# Proiect_TSC.net
KiCad netlist of a schematic drawn in EAGLE
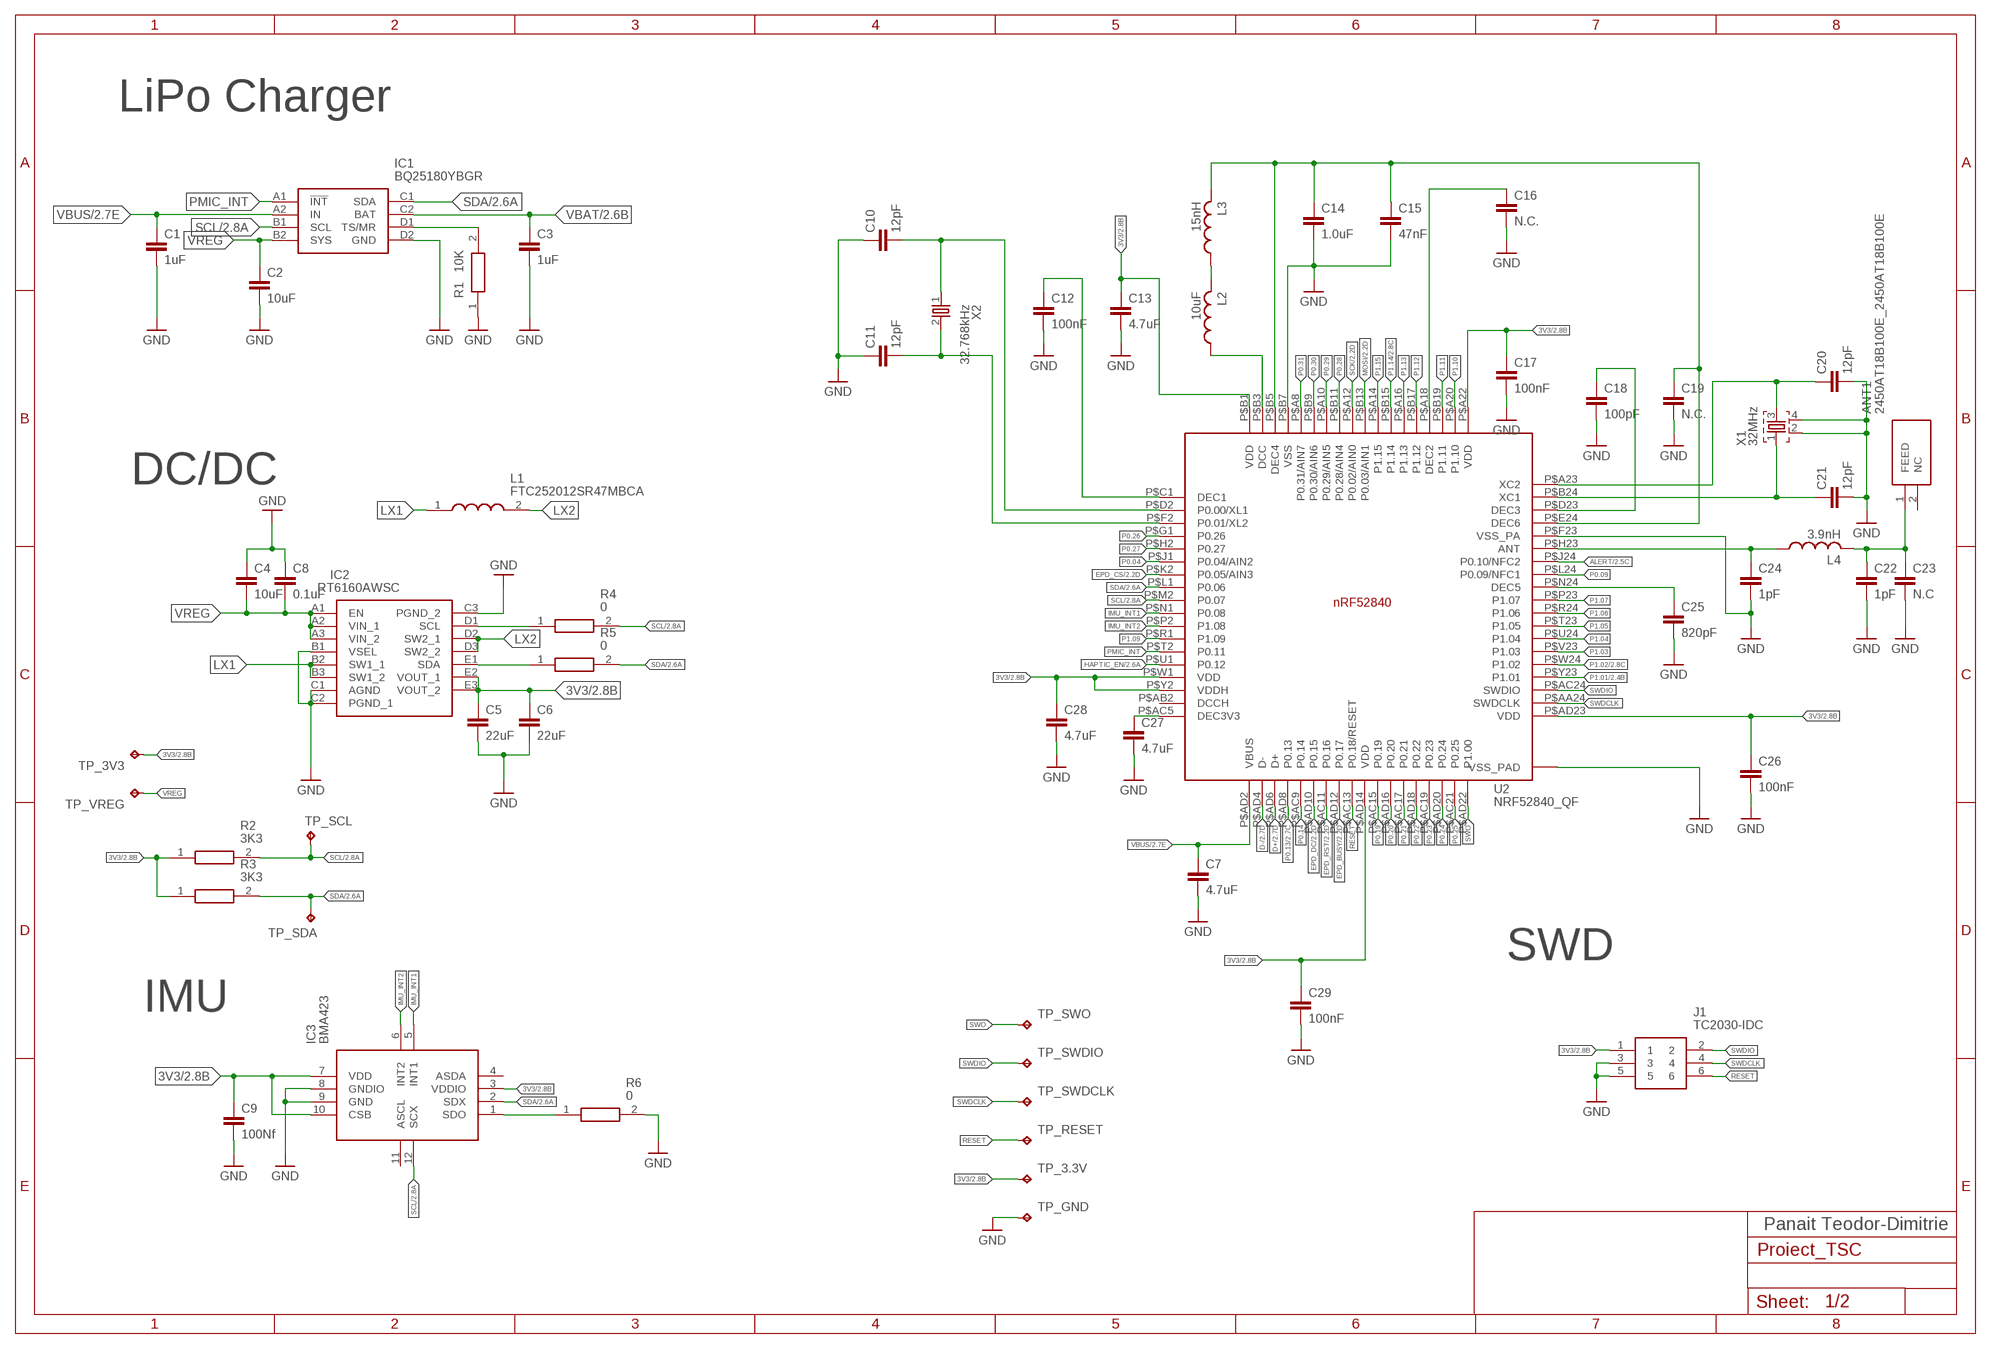
[diagram p0: schematic, sheet 1]
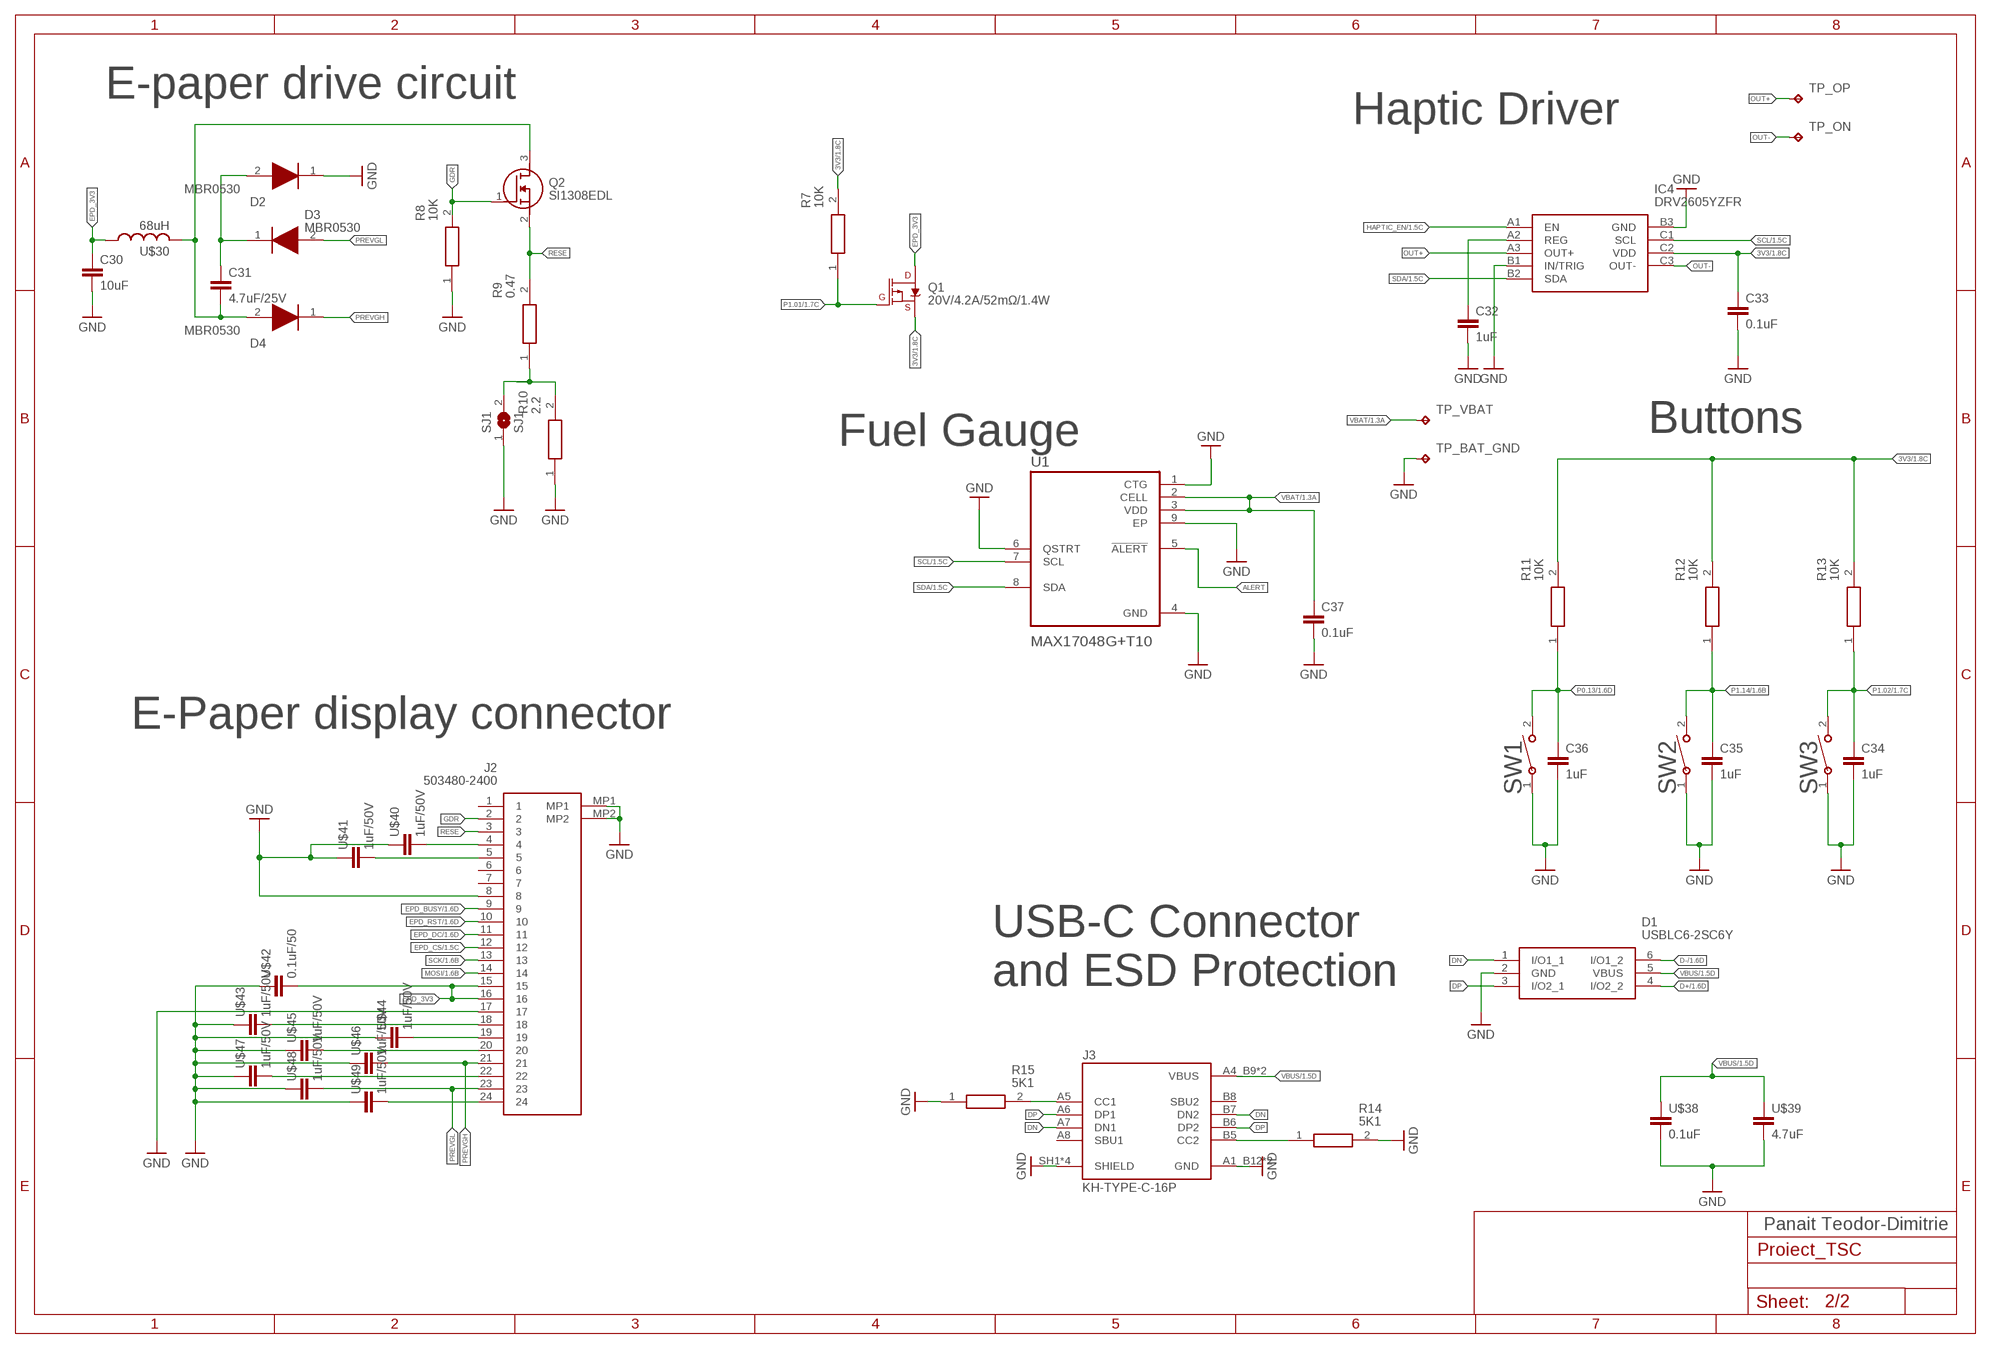
[diagram p1: schematic, sheet 2]

(export (version "E")
  (design (tool "Eeschema 10.0.6"))
  (components
    (comp (ref "C30")
      (value "10uF")
      (footprint "eagle-import:NORDIC_NRF_3_RESC0402_L")
      (libsource (lib "eagle-import") (part "NORDIC_NRF_3_CAPACITOR_0402_L"))
    )
    (comp (ref "C31")
      (value "4.7uF/25V")
      (footprint "eagle-import:NORDIC_NRF_3_RESC0402_L")
      (libsource (lib "eagle-import") (part "NORDIC_NRF_3_CAPACITOR_0402_L"))
    )
    (comp (ref "C32")
      (value "1uF")
      (footprint "eagle-import:NORDIC_NRF_3_RESC0402_L")
      (libsource (lib "eagle-import") (part "NORDIC_NRF_3_CAPACITOR_0402_L"))
    )
    (comp (ref "C33")
      (value "0.1uF")
      (footprint "eagle-import:NORDIC_NRF_3_RESC0201_L")
      (libsource (lib "eagle-import") (part "NORDIC_NRF_3_CAPACITOR_0201_L"))
    )
    (comp (ref "C34")
      (value "1uF")
      (footprint "eagle-import:NORDIC_NRF_3_RESC0402_L")
      (libsource (lib "eagle-import") (part "NORDIC_NRF_3_CAPACITOR_0402_L"))
    )
    (comp (ref "C35")
      (value "1uF")
      (footprint "eagle-import:NORDIC_NRF_3_RESC0402_L")
      (libsource (lib "eagle-import") (part "NORDIC_NRF_3_CAPACITOR_0402_L"))
    )
    (comp (ref "C36")
      (value "1uF")
      (footprint "eagle-import:NORDIC_NRF_3_RESC0402_L")
      (libsource (lib "eagle-import") (part "NORDIC_NRF_3_CAPACITOR_0402_L"))
    )
    (comp (ref "C37")
      (value "0.1uF")
      (footprint "eagle-import:NORDIC_NRF_3_RESC0201_L")
      (libsource (lib "eagle-import") (part "NORDIC_NRF_3_CAPACITOR_0201_L"))
    )
    (comp (ref "D1")
      (value "USBLC6-2SC6Y")
      (footprint "eagle-import:ESP32_C6_LIBRARY_3_SOT95P280X145-6N")
      (fields (field (name "MF") "STMicroelectronics"))
      (libsource (lib "eagle-import") (part "ESP32_C6_LIBRARY_3_USBLC6-2SC6Y"))
    )
    (comp (ref "D2")
      (value "MBR0530")
      (footprint "eagle-import:ESP32_C6_LIBRARY_5_SOD3716X135N")
      (fields (field (name "MF") "ON Semiconductor"))
      (libsource (lib "eagle-import") (part "ESP32_C6_LIBRARY_5_MBR0530"))
    )
    (comp (ref "D3")
      (value "MBR0530")
      (footprint "eagle-import:ESP32_C6_LIBRARY_5_SOD3716X135N")
      (fields (field (name "MF") "ON Semiconductor"))
      (libsource (lib "eagle-import") (part "ESP32_C6_LIBRARY_5_MBR0530"))
    )
    (comp (ref "D4")
      (value "MBR0530")
      (footprint "eagle-import:ESP32_C6_LIBRARY_5_SOD3716X135N")
      (fields (field (name "MF") "ON Semiconductor"))
      (libsource (lib "eagle-import") (part "ESP32_C6_LIBRARY_5_MBR0530"))
    )
    (comp (ref "IC4")
      (value "DRV2605YZFR")
      (footprint "eagle-import:DRV2605YZFR_BGA9C50P3X3_144X144X62")
      (libsource (lib "eagle-import") (part "DRV2605YZFR_DRV2605YZFR"))
    )
    (comp (ref "J2")
      (value "503480-2400")
      (footprint "eagle-import:503480-2400_5034802400")
      (fields (field (name "MOUSER_PART_NUMBER") "538-503480-2400"))
      (libsource (lib "eagle-import") (part "503480-2400_503480-2400"))
    )
    (comp (ref "J3")
      (value "KH-TYPE-C-16P")
      (footprint "eagle-import:KH-TYPE-C-16P_KINGHELM_KH-TYPE-C-16P")
      (fields (field (name "MF") "kinghelm"))
      (libsource (lib "eagle-import") (part "KH-TYPE-C-16P_KH-TYPE-C-16P"))
    )
    (comp (ref "Q1")
      (value "20V/4.2A/52mΩ/1.4W")
      (footprint "eagle-import:ESP32_C6_LIBRARY_4_ESP32_C6_LIBRARY_4_ESP32_C6_LIBRARY_4_ESP32_C6_LIBRARY_4_ESP32_WROVER_SPARKFUN-DISCRETESEMI_SOT23-3")
      (libsource (lib "eagle-import") (part "ESP32_C6_LIBRARY_4_ESP32_WROVER_SPARKFUN-DISCRETESEMI_MOSFET_PCH-DMG2305UX-7"))
    )
    (comp (ref "Q2")
      (value "SI1308EDL")
      (footprint "eagle-import:ESP32_C6_LIBRARY_6_SOT65P210X110-3N")
      (fields (field (name "MF") "Vishay Siliconix") (field (name "MP") "SI1308EDL-T1-GE3"))
      (libsource (lib "eagle-import") (part "ESP32_C6_LIBRARY_6_SI1308EDL-T1-GE3"))
    )
    (comp (ref "R7")
      (value "10K")
      (footprint "eagle-import:CPF0201D7K68C1_0201")
      (libsource (lib "eagle-import") (part "CPF0201D7K68C1_CPF0201D7K68C1"))
    )
    (comp (ref "R8")
      (value "10K")
      (footprint "eagle-import:CPF0201D7K68C1_0201")
      (libsource (lib "eagle-import") (part "CPF0201D7K68C1_CPF0201D7K68C1"))
    )
    (comp (ref "R9")
      (value "0.47")
      (footprint "eagle-import:CPF0201D7K68C1_0201")
      (libsource (lib "eagle-import") (part "CPF0201D7K68C1_CPF0201D7K68C1"))
    )
    (comp (ref "R10")
      (value "2.2")
      (footprint "eagle-import:CPF0201D7K68C1_0201")
      (libsource (lib "eagle-import") (part "CPF0201D7K68C1_CPF0201D7K68C1"))
    )
    (comp (ref "R11")
      (value "10K")
      (footprint "eagle-import:CPF0201D7K68C1_0201")
      (libsource (lib "eagle-import") (part "CPF0201D7K68C1_CPF0201D7K68C1"))
    )
    (comp (ref "R12")
      (value "10K")
      (footprint "eagle-import:CPF0201D7K68C1_0201")
      (libsource (lib "eagle-import") (part "CPF0201D7K68C1_CPF0201D7K68C1"))
    )
    (comp (ref "R13")
      (value "10K")
      (footprint "eagle-import:CPF0201D7K68C1_0201")
      (libsource (lib "eagle-import") (part "CPF0201D7K68C1_CPF0201D7K68C1"))
    )
    (comp (ref "R14")
      (value "5K1")
      (footprint "eagle-import:CPF0201D7K68C1_0201")
      (libsource (lib "eagle-import") (part "CPF0201D7K68C1_CPF0201D7K68C1"))
    )
    (comp (ref "R15")
      (value "5K1")
      (footprint "eagle-import:CPF0201D7K68C1_0201")
      (libsource (lib "eagle-import") (part "CPF0201D7K68C1_CPF0201D7K68C1"))
    )
    (comp (ref "SJ1")
      (value "SJ1")
      (footprint "eagle-import:ESP32_C6_LIBRARY_7_JUMPER_SJ")
      (libsource (lib "eagle-import") (part "ESP32_C6_LIBRARY_7_JUMPER_SJ"))
    )
    (comp (ref "SW1")
      (value "SW1")
      (footprint "eagle-import:2025-10-22_07-23-44_LIBRARY_SW_EVP-AKE31A_PAN")
      (fields
        (field (name "MANUFACTURER_PART_NUMBER") "EVP-AKE31A")
        (field (name "COPYRIGHT") "Copyright (C) 2025 Ultra Librarian. All rights reserved.")
      )
      (libsource (lib "eagle-import") (part "2025-10-22_07-23-44_LIBRARY_EVP-AKE31ASW_EVP-AKE31A_PAN"))
    )
    (comp (ref "SW2")
      (value "2025-10-22_07-23-44_LIBRARY_EVP-AKE31ASW_EVP-AKE31A_PAN")
      (footprint "eagle-import:2025-10-22_07-23-44_LIBRARY_SW_EVP-AKE31A_PAN")
      (fields
        (field (name "MANUFACTURER_PART_NUMBER") "EVP-AKE31A")
        (field (name "COPYRIGHT") "Copyright (C) 2025 Ultra Librarian. All rights reserved.")
      )
      (libsource (lib "eagle-import") (part "2025-10-22_07-23-44_LIBRARY_EVP-AKE31ASW_EVP-AKE31A_PAN"))
    )
    (comp (ref "SW3")
      (value "2025-10-22_07-23-44_LIBRARY_EVP-AKE31ASW_EVP-AKE31A_PAN")
      (footprint "eagle-import:2025-10-22_07-23-44_LIBRARY_SW_EVP-AKE31A_PAN")
      (fields
        (field (name "MANUFACTURER_PART_NUMBER") "EVP-AKE31A")
        (field (name "COPYRIGHT") "Copyright (C) 2025 Ultra Librarian. All rights reserved.")
      )
      (libsource (lib "eagle-import") (part "2025-10-22_07-23-44_LIBRARY_EVP-AKE31ASW_EVP-AKE31A_PAN"))
    )
    (comp (ref "TP_BAT_GND")
      (value "HECTOR_WATCH_1_TPTP20R")
      (footprint "eagle-import:HECTOR_WATCH_1_TP20R")
      (libsource (lib "eagle-import") (part "HECTOR_WATCH_1_TPTP20R"))
    )
    (comp (ref "TP_ON")
      (value "HECTOR_WATCH_1_TPTP20R")
      (footprint "eagle-import:HECTOR_WATCH_1_TP20R")
      (libsource (lib "eagle-import") (part "HECTOR_WATCH_1_TPTP20R"))
    )
    (comp (ref "TP_OP")
      (value "HECTOR_WATCH_1_TPTP20R")
      (footprint "eagle-import:HECTOR_WATCH_1_TP20R")
      (libsource (lib "eagle-import") (part "HECTOR_WATCH_1_TPTP20R"))
    )
    (comp (ref "TP_VBAT")
      (value "HECTOR_WATCH_1_TPTP20R")
      (footprint "eagle-import:HECTOR_WATCH_1_TP20R")
      (libsource (lib "eagle-import") (part "HECTOR_WATCH_1_TPTP20R"))
    )
    (comp (ref "U$30")
      (value "68uH")
      (footprint "eagle-import:NORDIC_NRF_2_RESC0201_L")
      (libsource (lib "eagle-import") (part "NORDIC_NRF_2_INDUCTOR_0201_L"))
    )
    (comp (ref "U$38")
      (value "0.1uF")
      (footprint "eagle-import:NORDIC_NRF_3_RESC0201_L")
      (libsource (lib "eagle-import") (part "NORDIC_NRF_3_CAPACITOR_0201_L"))
    )
    (comp (ref "U$39")
      (value "4.7uF")
      (footprint "eagle-import:NORDIC_NRF_3_RESC0402_L")
      (libsource (lib "eagle-import") (part "NORDIC_NRF_3_CAPACITOR_0402_L"))
    )
    (comp (ref "U$40")
      (value "1uF/50V")
      (footprint "eagle-import:NORDIC_NRF_3_RESC0402_L")
      (libsource (lib "eagle-import") (part "NORDIC_NRF_3_CAPACITOR_0402_L"))
    )
    (comp (ref "U$41")
      (value "1uF/50V")
      (footprint "eagle-import:NORDIC_NRF_3_RESC0402_L")
      (libsource (lib "eagle-import") (part "NORDIC_NRF_3_CAPACITOR_0402_L"))
    )
    (comp (ref "U$42")
      (value "0.1uF/50")
      (footprint "eagle-import:NORDIC_NRF_3_RESC0201_L")
      (libsource (lib "eagle-import") (part "NORDIC_NRF_3_CAPACITOR_0201_L"))
    )
    (comp (ref "U$43")
      (value "1uF/50V")
      (footprint "eagle-import:NORDIC_NRF_3_RESC0402_L")
      (libsource (lib "eagle-import") (part "NORDIC_NRF_3_CAPACITOR_0402_L"))
    )
    (comp (ref "U$44")
      (value "1uF/50V")
      (footprint "eagle-import:NORDIC_NRF_3_RESC0402_L")
      (libsource (lib "eagle-import") (part "NORDIC_NRF_3_CAPACITOR_0402_L"))
    )
    (comp (ref "U$45")
      (value "1uF/50V")
      (footprint "eagle-import:NORDIC_NRF_3_RESC0402_L")
      (libsource (lib "eagle-import") (part "NORDIC_NRF_3_CAPACITOR_0402_L"))
    )
    (comp (ref "U$46")
      (value "1uF/50V")
      (footprint "eagle-import:NORDIC_NRF_3_RESC0402_L")
      (libsource (lib "eagle-import") (part "NORDIC_NRF_3_CAPACITOR_0402_L"))
    )
    (comp (ref "U$47")
      (value "1uF/50V")
      (footprint "eagle-import:NORDIC_NRF_3_RESC0402_L")
      (libsource (lib "eagle-import") (part "NORDIC_NRF_3_CAPACITOR_0402_L"))
    )
    (comp (ref "U$48")
      (value "1uF/50V")
      (footprint "eagle-import:NORDIC_NRF_3_RESC0402_L")
      (libsource (lib "eagle-import") (part "NORDIC_NRF_3_CAPACITOR_0402_L"))
    )
    (comp (ref "U$49")
      (value "1uF/50V")
      (footprint "eagle-import:NORDIC_NRF_3_RESC0402_L")
      (libsource (lib "eagle-import") (part "NORDIC_NRF_3_CAPACITOR_0402_L"))
    )
    (comp (ref "U1")
      (value "MAX17048G+T10")
      (footprint "eagle-import:ESP32_C6_LIBRARY_SON50P200X200X80-9N")
      (fields (field (name "MF") "Analog Devices"))
      (libsource (lib "eagle-import") (part "ESP32_C6_LIBRARY_MAX17048G+T10"))
    )
    (comp (ref "ANT1")
      (value "2450AT18B100E_2450AT18B100E")
      (footprint "eagle-import:2450AT18B100E_ANTC3216X140N")
      (fields
        (field (name "ARROW_PART_NUMBER") "2450AT18B100E")
        (field (name "MOUSER_PART_NUMBER") "609-2450AT18B100E")
      )
      (libsource (lib "eagle-import") (part "2450AT18B100E_2450AT18B100E"))
    )
    (comp (ref "C1")
      (value "1uF")
      (footprint "eagle-import:PERFECT_0402_0402")
      (libsource (lib "eagle-import") (part "PERFECT_0402_CAP_0402"))
    )
    (comp (ref "C2")
      (value "10uF")
      (footprint "eagle-import:PERFECT_0402_0402")
      (libsource (lib "eagle-import") (part "PERFECT_0402_CAP_0402"))
    )
    (comp (ref "C3")
      (value "1uF")
      (footprint "eagle-import:PERFECT_0402_0402")
      (libsource (lib "eagle-import") (part "PERFECT_0402_CAP_0402"))
    )
    (comp (ref "C4")
      (value "10uF")
      (footprint "eagle-import:PERFECT_0402_0402")
      (libsource (lib "eagle-import") (part "PERFECT_0402_CAP_0402"))
    )
    (comp (ref "C5")
      (value "22uF")
      (footprint "eagle-import:PERFECT_0402_0402")
      (libsource (lib "eagle-import") (part "PERFECT_0402_CAP_0402"))
    )
    (comp (ref "C6")
      (value "22uF")
      (footprint "eagle-import:PERFECT_0402_0402")
      (libsource (lib "eagle-import") (part "PERFECT_0402_CAP_0402"))
    )
    (comp (ref "C7")
      (value "4.7uF")
      (footprint "eagle-import:PERFECT_0402_0402")
      (libsource (lib "eagle-import") (part "PERFECT_0402_CAP_0402"))
    )
    (comp (ref "C8")
      (value "0.1uF")
      (footprint "eagle-import:NORDIC_NRF_3_RESC0201_L")
      (libsource (lib "eagle-import") (part "NORDIC_NRF_3_CAPACITOR_0201_L"))
    )
    (comp (ref "C9")
      (value "100Nf")
      (footprint "eagle-import:NORDIC_NRF_3_RESC0201_L")
      (libsource (lib "eagle-import") (part "NORDIC_NRF_3_CAPACITOR_0201_L"))
    )
    (comp (ref "C10")
      (value "12pF")
      (footprint "eagle-import:NORDIC_NRF_3_RESC0201_L")
      (libsource (lib "eagle-import") (part "NORDIC_NRF_3_CAPACITOR_0201_L"))
    )
    (comp (ref "C11")
      (value "12pF")
      (footprint "eagle-import:NORDIC_NRF_3_RESC0201_L")
      (libsource (lib "eagle-import") (part "NORDIC_NRF_3_CAPACITOR_0201_L"))
    )
    (comp (ref "C12")
      (value "100nF")
      (footprint "eagle-import:NORDIC_NRF_3_RESC0201_L")
      (libsource (lib "eagle-import") (part "NORDIC_NRF_3_CAPACITOR_0201_L"))
    )
    (comp (ref "C13")
      (value "4.7uF")
      (footprint "eagle-import:NORDIC_NRF_3_RESC0402_L")
      (libsource (lib "eagle-import") (part "NORDIC_NRF_3_CAPACITOR_0402_L"))
    )
    (comp (ref "C14")
      (value "1.0uF")
      (footprint "eagle-import:NORDIC_NRF_3_RESC0402_L")
      (libsource (lib "eagle-import") (part "NORDIC_NRF_3_CAPACITOR_0402_L"))
    )
    (comp (ref "C15")
      (value "47nF")
      (footprint "eagle-import:NORDIC_NRF_3_RESC0201_L")
      (libsource (lib "eagle-import") (part "NORDIC_NRF_3_CAPACITOR_0201_L"))
    )
    (comp (ref "C16")
      (value "N.C.")
      (footprint "eagle-import:NORDIC_NRF_3_RESC0201_L")
      (libsource (lib "eagle-import") (part "NORDIC_NRF_3_CAPACITOR_0201_L"))
    )
    (comp (ref "C17")
      (value "100nF")
      (footprint "eagle-import:NORDIC_NRF_3_RESC0201_L")
      (libsource (lib "eagle-import") (part "NORDIC_NRF_3_CAPACITOR_0201_L"))
    )
    (comp (ref "C18")
      (value "100pF")
      (footprint "eagle-import:NORDIC_NRF_3_RESC0201_L")
      (libsource (lib "eagle-import") (part "NORDIC_NRF_3_CAPACITOR_0201_L"))
    )
    (comp (ref "C19")
      (value "N.C.")
      (footprint "eagle-import:NORDIC_NRF_3_RESC0201_L")
      (libsource (lib "eagle-import") (part "NORDIC_NRF_3_CAPACITOR_0201_L"))
    )
    (comp (ref "C20")
      (value "12pF")
      (footprint "eagle-import:NORDIC_NRF_3_RESC0201_L")
      (libsource (lib "eagle-import") (part "NORDIC_NRF_3_CAPACITOR_0201_L"))
    )
    (comp (ref "C21")
      (value "12pF")
      (footprint "eagle-import:NORDIC_NRF_3_RESC0201_L")
      (libsource (lib "eagle-import") (part "NORDIC_NRF_3_CAPACITOR_0201_L"))
    )
    (comp (ref "C22")
      (value "1pF")
      (footprint "eagle-import:NORDIC_NRF_3_RESC0201_L")
      (libsource (lib "eagle-import") (part "NORDIC_NRF_3_CAPACITOR_0201_L"))
    )
    (comp (ref "C23")
      (value "N.C")
      (footprint "eagle-import:NORDIC_NRF_3_RESC0201_L")
      (libsource (lib "eagle-import") (part "NORDIC_NRF_3_CAPACITOR_0201_L"))
    )
    (comp (ref "C24")
      (value "1pF")
      (footprint "eagle-import:NORDIC_NRF_3_RESC0201_L")
      (libsource (lib "eagle-import") (part "NORDIC_NRF_3_CAPACITOR_0201_L"))
    )
    (comp (ref "C25")
      (value "820pF")
      (footprint "eagle-import:NORDIC_NRF_3_RESC0201_L")
      (libsource (lib "eagle-import") (part "NORDIC_NRF_3_CAPACITOR_0201_L"))
    )
    (comp (ref "C26")
      (value "100nF")
      (footprint "eagle-import:NORDIC_NRF_3_RESC0201_L")
      (libsource (lib "eagle-import") (part "NORDIC_NRF_3_CAPACITOR_0201_L"))
    )
    (comp (ref "C27")
      (value "4.7uF")
      (footprint "eagle-import:NORDIC_NRF_3_RESC0402_L")
      (libsource (lib "eagle-import") (part "NORDIC_NRF_3_CAPACITOR_0402_L"))
    )
    (comp (ref "C28")
      (value "4.7uF")
      (footprint "eagle-import:NORDIC_NRF_3_RESC0402_L")
      (libsource (lib "eagle-import") (part "NORDIC_NRF_3_CAPACITOR_0402_L"))
    )
    (comp (ref "C29")
      (value "100nF")
      (footprint "eagle-import:NORDIC_NRF_3_RESC0201_L")
      (libsource (lib "eagle-import") (part "NORDIC_NRF_3_CAPACITOR_0201_L"))
    )
    (comp (ref "IC1")
      (value "BQ25180YBGR")
      (footprint "eagle-import:BQ25180YBGR_BGA8C40P2X4_100X155X50")
      (fields (field (name "MOUSER_PART_NUMBER") "595-BQ25180YBGR"))
      (libsource (lib "eagle-import") (part "BQ25180YBGR_BQ25180YBGR"))
    )
    (comp (ref "IC2")
      (value "RT6160AWSC")
      (footprint "eagle-import:RT6160AWSC_BGA15C40P3X5_140X230X60")
      (fields (field (name "MOUSER_PART_NUMBER") "835-RT6160AWSC"))
      (libsource (lib "eagle-import") (part "RT6160AWSC_RT6160AWSC"))
    )
    (comp (ref "IC3")
      (value "BMA423")
      (footprint "eagle-import:BMA423_BMA423")
      (fields (field (name "MOUSER_PART_NUMBER") "262-BMA423"))
      (libsource (lib "eagle-import") (part "BMA423_BMA423"))
    )
    (comp (ref "J1")
      (value "TC2030-IDC")
      (footprint "eagle-import:TC2030-IDC_TC2030IDC")
      (libsource (lib "eagle-import") (part "TC2030-IDC_TC2030-IDC"))
    )
    (comp (ref "L1")
      (value "FTC252012SR47MBCA")
      (footprint "eagle-import:MLP2016SR47MT0S1_INDC2016X100N")
      (libsource (lib "eagle-import") (part "MLP2016SR47MT0S1_FTC252012SR47MBCA"))
    )
    (comp (ref "L2")
      (value "10uF")
      (footprint "eagle-import:NORDIC_NRF_2_RESC0201_L")
      (libsource (lib "eagle-import") (part "NORDIC_NRF_2_INDUCTOR_0201_L"))
    )
    (comp (ref "L3")
      (value "15nH")
      (footprint "eagle-import:NORDIC_NRF_2_RESC0201_L")
      (libsource (lib "eagle-import") (part "NORDIC_NRF_2_INDUCTOR_0201_L"))
    )
    (comp (ref "L4")
      (value "3.9nH")
      (footprint "eagle-import:NORDIC_NRF_2_RESC0201_L")
      (libsource (lib "eagle-import") (part "NORDIC_NRF_2_INDUCTOR_0201_L"))
    )
    (comp (ref "R1")
      (value "10K")
      (footprint "eagle-import:CPF0201D7K68C1_0201")
      (libsource (lib "eagle-import") (part "CPF0201D7K68C1_CPF0201D7K68C1"))
    )
    (comp (ref "R2")
      (value "3K3")
      (footprint "eagle-import:CPF0201D7K68C1_0201")
      (libsource (lib "eagle-import") (part "CPF0201D7K68C1_CPF0201D7K68C1"))
    )
    (comp (ref "R3")
      (value "3K3")
      (footprint "eagle-import:CPF0201D7K68C1_0201")
      (libsource (lib "eagle-import") (part "CPF0201D7K68C1_CPF0201D7K68C1"))
    )
    (comp (ref "R4")
      (value "0")
      (footprint "eagle-import:CPF0201D7K68C1_0201")
      (libsource (lib "eagle-import") (part "CPF0201D7K68C1_CPF0201D7K68C1"))
    )
    (comp (ref "R5")
      (value "0")
      (footprint "eagle-import:CPF0201D7K68C1_0201")
      (libsource (lib "eagle-import") (part "CPF0201D7K68C1_CPF0201D7K68C1"))
    )
    (comp (ref "R6")
      (value "0")
      (footprint "eagle-import:CPF0201D7K68C1_0201")
      (libsource (lib "eagle-import") (part "CPF0201D7K68C1_CPF0201D7K68C1"))
    )
    (comp (ref "TP_3.3V")
      (value "HECTOR_WATCH_1_TPTP20R")
      (footprint "eagle-import:HECTOR_WATCH_1_TP20R")
      (libsource (lib "eagle-import") (part "HECTOR_WATCH_1_TPTP20R"))
    )
    (comp (ref "TP_3V3")
      (value "HECTOR_WATCH_1_TPTP20R")
      (footprint "eagle-import:HECTOR_WATCH_1_TP20R")
      (libsource (lib "eagle-import") (part "HECTOR_WATCH_1_TPTP20R"))
    )
    (comp (ref "TP_GND")
      (value "HECTOR_WATCH_1_TPTP20R")
      (footprint "eagle-import:HECTOR_WATCH_1_TP20R")
      (libsource (lib "eagle-import") (part "HECTOR_WATCH_1_TPTP20R"))
    )
    (comp (ref "TP_RESET")
      (value "HECTOR_WATCH_1_TPTP20R")
      (footprint "eagle-import:HECTOR_WATCH_1_TP20R")
      (libsource (lib "eagle-import") (part "HECTOR_WATCH_1_TPTP20R"))
    )
    (comp (ref "TP_SCL")
      (value "HECTOR_WATCH_1_TPTP20R")
      (footprint "eagle-import:HECTOR_WATCH_1_TP20R")
      (libsource (lib "eagle-import") (part "HECTOR_WATCH_1_TPTP20R"))
    )
    (comp (ref "TP_SDA")
      (value "HECTOR_WATCH_1_TPTP20R")
      (footprint "eagle-import:HECTOR_WATCH_1_TP20R")
      (libsource (lib "eagle-import") (part "HECTOR_WATCH_1_TPTP20R"))
    )
    (comp (ref "TP_SWDCLK")
      (value "HECTOR_WATCH_1_TPTP20R")
      (footprint "eagle-import:HECTOR_WATCH_1_TP20R")
      (libsource (lib "eagle-import") (part "HECTOR_WATCH_1_TPTP20R"))
    )
    (comp (ref "TP_SWDIO")
      (value "HECTOR_WATCH_1_TPTP20R")
      (footprint "eagle-import:HECTOR_WATCH_1_TP20R")
      (libsource (lib "eagle-import") (part "HECTOR_WATCH_1_TPTP20R"))
    )
    (comp (ref "TP_SWO")
      (value "HECTOR_WATCH_1_TPTP20R")
      (footprint "eagle-import:HECTOR_WATCH_1_TP20R")
      (libsource (lib "eagle-import") (part "HECTOR_WATCH_1_TPTP20R"))
    )
    (comp (ref "TP_VREG")
      (value "HECTOR_WATCH_1_TPTP20R")
      (footprint "eagle-import:HECTOR_WATCH_1_TP20R")
      (libsource (lib "eagle-import") (part "HECTOR_WATCH_1_TPTP20R"))
    )
    (comp (ref "U2")
      (value "NRF52840_QF")
      (footprint "eagle-import:NORDIC_NRF_4_AQFN50P700X700X85_HS-74N")
      (libsource (lib "eagle-import") (part "NORDIC_NRF_4_NRF52840_QF"))
    )
    (comp (ref "X1")
      (value "32MHz")
      (footprint "eagle-import:NORDIC_NRF_BT-XTAL_2016_N")
      (libsource (lib "eagle-import") (part "NORDIC_NRF_XTAL_32MHZ"))
    )
    (comp (ref "X2")
      (value "32.768kHz")
      (footprint "eagle-import:NORDIC_NRF_1_XTAL_3215_N")
      (libsource (lib "eagle-import") (part "NORDIC_NRF_1_XTAL_32KHZ"))
    )
  )
  (nets
    (net (code "1") (name "3V3") (class "Default")
      (node (ref "C13") (pin "1") (pinfunction "1_1") (pintype "passive"))
      (node (ref "C17") (pin "1") (pinfunction "1_1") (pintype "passive"))
      (node (ref "C26") (pin "1") (pinfunction "1_1") (pintype "passive"))
      (node (ref "C28") (pin "1") (pinfunction "1_1") (pintype "passive"))
      (node (ref "C29") (pin "1") (pinfunction "1_1") (pintype "passive"))
      (node (ref "C33") (pin "1") (pinfunction "1_1") (pintype "passive"))
      (node (ref "C5") (pin "1") (pinfunction "1_1") (pintype "passive"))
      (node (ref "C6") (pin "1") (pinfunction "1_1") (pintype "passive"))
      (node (ref "C9") (pin "1") (pinfunction "1_1") (pintype "passive"))
      (node (ref "IC2") (pin "E2") (pinfunction "VOUT_1_E2") (pintype "bidirectional"))
      (node (ref "IC2") (pin "E3") (pinfunction "VOUT_2_E3") (pintype "bidirectional"))
      (node (ref "IC3") (pin "10") (pinfunction "CSB_10") (pintype "bidirectional"))
      (node (ref "IC3") (pin "3") (pinfunction "VDDIO_3") (pintype "bidirectional"))
      (node (ref "IC3") (pin "7") (pinfunction "VDD_7") (pintype "bidirectional"))
      (node (ref "IC4") (pin "C2") (pinfunction "VDD_C2") (pintype "bidirectional"))
      (node (ref "J1") (pin "1") (pinfunction "1_1") (pintype "bidirectional"))
      (node (ref "Q1") (pin "2") (pinfunction "S_2") (pintype "bidirectional"))
      (node (ref "R11") (pin "2") (pinfunction "2_2") (pintype "bidirectional"))
      (node (ref "R12") (pin "2") (pinfunction "2_2") (pintype "bidirectional"))
      (node (ref "R13") (pin "2") (pinfunction "2_2") (pintype "bidirectional"))
      (node (ref "R2") (pin "1") (pinfunction "1_1") (pintype "bidirectional"))
      (node (ref "R3") (pin "1") (pinfunction "1_1") (pintype "bidirectional"))
      (node (ref "R7") (pin "2") (pinfunction "2_2") (pintype "bidirectional"))
      (node (ref "TP_3.3V") (pin "TP") (pinfunction "TP_TP") (pintype "input"))
      (node (ref "TP_3V3") (pin "TP") (pinfunction "TP_TP") (pintype "input"))
      (node (ref "U2") (pin "P$A22") (pinfunction "VDD_P$A22") (pintype "power_in"))
      (node (ref "U2") (pin "P$AD14") (pinfunction "VDD_P$AD14") (pintype "power_in"))
      (node (ref "U2") (pin "P$AD23") (pinfunction "VDD_P$AD23") (pintype "power_in"))
      (node (ref "U2") (pin "P$B1") (pinfunction "VDD_P$B1") (pintype "power_in"))
      (node (ref "U2") (pin "P$W1") (pinfunction "VDD_P$W1") (pintype "power_in"))
      (node (ref "U2") (pin "P$Y2") (pinfunction "VDDH_P$Y2") (pintype "power_in"))
    )
    (net (code "2") (name "ALERT") (class "Default")
      (node (ref "U1") (pin "5") (pinfunction "~{ALERT}_5") (pintype "output"))
    )
    (net (code "3") (name "ALERT{slash}2.5C") (class "Default")
      (node (ref "U2") (pin "P$J24") (pinfunction "P0.10/NFC2_P$J24") (pintype "bidirectional"))
    )
    (net (code "4") (name "D+") (class "Default")
      (node (ref "D1") (pin "4") (pinfunction "I/O2_2_4") (pintype "bidirectional"))
      (node (ref "U2") (pin "P$AD6") (pinfunction "D+_P$AD6") (pintype "bidirectional"))
    )
    (net (code "5") (name "D-") (class "Default")
      (node (ref "D1") (pin "6") (pinfunction "I/O1_2_6") (pintype "bidirectional"))
      (node (ref "U2") (pin "P$AD4") (pinfunction "D-_P$AD4") (pintype "bidirectional"))
    )
    (net (code "6") (name "DN") (class "Default")
      (node (ref "D1") (pin "1") (pinfunction "I/O1_1_1") (pintype "bidirectional"))
      (node (ref "J3") (pin "A7") (pinfunction "DN1_A7") (pintype "bidirectional"))
      (node (ref "J3") (pin "B7") (pinfunction "DN2_B7") (pintype "bidirectional"))
    )
    (net (code "7") (name "DP") (class "Default")
      (node (ref "D1") (pin "3") (pinfunction "I/O2_1_3") (pintype "bidirectional"))
      (node (ref "J3") (pin "A6") (pinfunction "DP1_A6") (pintype "bidirectional"))
      (node (ref "J3") (pin "B6") (pinfunction "DP2_B6") (pintype "bidirectional"))
    )
    (net (code "8") (name "EPD_3V3") (class "Default")
      (node (ref "C30") (pin "1") (pinfunction "1_1") (pintype "passive"))
      (node (ref "J2") (pin "15") (pinfunction "15_15") (pintype "bidirectional"))
      (node (ref "J2") (pin "16") (pinfunction "16_16") (pintype "bidirectional"))
      (node (ref "Q1") (pin "3") (pinfunction "D_3") (pintype "bidirectional"))
      (node (ref "U$30") (pin "1") (pinfunction "1_1") (pintype "passive"))
      (node (ref "U$42") (pin "2") (pinfunction "2_2") (pintype "passive"))
    )
    (net (code "9") (name "EPD_BUSY") (class "Default")
      (node (ref "J2") (pin "9") (pinfunction "9_9") (pintype "bidirectional"))
      (node (ref "U2") (pin "P$AD12") (pinfunction "P0.17_P$AD12") (pintype "bidirectional"))
    )
    (net (code "10") (name "EPD_CS") (class "Default")
      (node (ref "J2") (pin "12") (pinfunction "12_12") (pintype "bidirectional"))
      (node (ref "U2") (pin "P$K2") (pinfunction "P0.05/AIN3_P$K2") (pintype "bidirectional"))
    )
    (net (code "11") (name "EPD_DC") (class "Default")
      (node (ref "J2") (pin "11") (pinfunction "11_11") (pintype "bidirectional"))
      (node (ref "U2") (pin "P$AD10") (pinfunction "P0.15_P$AD10") (pintype "bidirectional"))
    )
    (net (code "12") (name "EPD_RST") (class "Default")
      (node (ref "J2") (pin "10") (pinfunction "10_10") (pintype "bidirectional"))
      (node (ref "U2") (pin "P$AC11") (pinfunction "P0.16_P$AC11") (pintype "bidirectional"))
    )
    (net (code "13") (name "GDR") (class "Default")
      (node (ref "J2") (pin "2") (pinfunction "2_2") (pintype "bidirectional"))
      (node (ref "Q2") (pin "1") (pinfunction "G_1") (pintype "bidirectional"))
      (node (ref "R8") (pin "2") (pinfunction "2_2") (pintype "bidirectional"))
    )
    (net (code "14") (name "GND") (class "Default")
      (node (ref "C1") (pin "2") (pinfunction "2_2") (pintype "passive"))
      (node (ref "C10") (pin "1") (pinfunction "1_1") (pintype "passive"))
      (node (ref "C11") (pin "1") (pinfunction "1_1") (pintype "passive"))
      (node (ref "C12") (pin "2") (pinfunction "2_2") (pintype "passive"))
      (node (ref "C13") (pin "2") (pinfunction "2_2") (pintype "passive"))
      (node (ref "C14") (pin "2") (pinfunction "2_2") (pintype "passive"))
      (node (ref "C15") (pin "2") (pinfunction "2_2") (pintype "passive"))
      (node (ref "C16") (pin "2") (pinfunction "2_2") (pintype "passive"))
      (node (ref "C17") (pin "2") (pinfunction "2_2") (pintype "passive"))
      (node (ref "C18") (pin "2") (pinfunction "2_2") (pintype "passive"))
      (node (ref "C19") (pin "2") (pinfunction "2_2") (pintype "passive"))
      (node (ref "C2") (pin "2") (pinfunction "2_2") (pintype "passive"))
      (node (ref "C20") (pin "2") (pinfunction "2_2") (pintype "passive"))
      (node (ref "C21") (pin "2") (pinfunction "2_2") (pintype "passive"))
      (node (ref "C22") (pin "2") (pinfunction "2_2") (pintype "passive"))
      (node (ref "C23") (pin "2") (pinfunction "2_2") (pintype "passive"))
      (node (ref "C24") (pin "2") (pinfunction "2_2") (pintype "passive"))
      (node (ref "C25") (pin "2") (pinfunction "2_2") (pintype "passive"))
      (node (ref "C26") (pin "2") (pinfunction "2_2") (pintype "passive"))
      (node (ref "C27") (pin "2") (pinfunction "2_2") (pintype "passive"))
      (node (ref "C28") (pin "2") (pinfunction "2_2") (pintype "passive"))
      (node (ref "C29") (pin "2") (pinfunction "2_2") (pintype "passive"))
      (node (ref "C3") (pin "2") (pinfunction "2_2") (pintype "passive"))
      (node (ref "C30") (pin "2") (pinfunction "2_2") (pintype "passive"))
      (node (ref "C32") (pin "2") (pinfunction "2_2") (pintype "passive"))
      (node (ref "C33") (pin "2") (pinfunction "2_2") (pintype "passive"))
      (node (ref "C34") (pin "2") (pinfunction "2_2") (pintype "passive"))
      (node (ref "C35") (pin "2") (pinfunction "2_2") (pintype "passive"))
      (node (ref "C36") (pin "2") (pinfunction "2_2") (pintype "passive"))
      (node (ref "C37") (pin "2") (pinfunction "2_2") (pintype "passive"))
      (node (ref "C4") (pin "1") (pinfunction "1_1") (pintype "passive"))
      (node (ref "C5") (pin "2") (pinfunction "2_2") (pintype "passive"))
      (node (ref "C6") (pin "2") (pinfunction "2_2") (pintype "passive"))
      (node (ref "C7") (pin "2") (pinfunction "2_2") (pintype "passive"))
      (node (ref "C8") (pin "1") (pinfunction "1_1") (pintype "passive"))
      (node (ref "C9") (pin "2") (pinfunction "2_2") (pintype "passive"))
      (node (ref "D1") (pin "2") (pinfunction "GND_2") (pintype "bidirectional"))
      (node (ref "D2") (pin "1") (pinfunction "K_1") (pintype "bidirectional"))
      (node (ref "IC1") (pin "D2") (pinfunction "GND_D2") (pintype "bidirectional"))
      (node (ref "IC2") (pin "B1") (pinfunction "VSEL_B1") (pintype "bidirectional"))
      (node (ref "IC2") (pin "C1") (pinfunction "AGND_C1") (pintype "bidirectional"))
      (node (ref "IC2") (pin "C2") (pinfunction "PGND_1_C2") (pintype "bidirectional"))
      (node (ref "IC2") (pin "C3") (pinfunction "PGND_2_C3") (pintype "bidirectional"))
      (node (ref "IC3") (pin "8") (pinfunction "GNDIO_8") (pintype "bidirectional"))
      (node (ref "IC3") (pin "9") (pinfunction "GND_9") (pintype "bidirectional"))
      (node (ref "IC4") (pin "B1") (pinfunction "IN/TRIG_B1") (pintype "bidirectional"))
      (node (ref "IC4") (pin "B3") (pinfunction "GND_B3") (pintype "bidirectional"))
      (node (ref "J1") (pin "3") (pinfunction "3_3") (pintype "bidirectional"))
      (node (ref "J1") (pin "5") (pinfunction "5_5") (pintype "bidirectional"))
      (node (ref "J2") (pin "17") (pinfunction "17_17") (pintype "bidirectional"))
      (node (ref "J2") (pin "8") (pinfunction "8_8") (pintype "bidirectional"))
      (node (ref "J2") (pin "MP1") (pinfunction "MP1_MP1") (pintype "bidirectional"))
      (node (ref "J2") (pin "MP2") (pinfunction "MP2_MP2") (pintype "bidirectional"))
      (node (ref "J3") (pin "A12_B1") (pinfunction "GND_A12_B1") (pintype "power_in"))
      (node (ref "J3") (pin "A1_B12") (pinfunction "GND_A1_B12") (pintype "power_in"))
      (node (ref "J3") (pin "SH1") (pinfunction "SHIELD_SH1") (pintype "passive"))
      (node (ref "J3") (pin "SH2") (pinfunction "SHIELD_SH2") (pintype "passive"))
      (node (ref "J3") (pin "SH3") (pinfunction "SHIELD_SH3") (pintype "passive"))
      (node (ref "J3") (pin "SH4") (pinfunction "SHIELD_SH4") (pintype "passive"))
      (node (ref "R1") (pin "1") (pinfunction "1_1") (pintype "bidirectional"))
      (node (ref "R10") (pin "1") (pinfunction "1_1") (pintype "bidirectional"))
      (node (ref "R14") (pin "2") (pinfunction "2_2") (pintype "bidirectional"))
      (node (ref "R15") (pin "1") (pinfunction "1_1") (pintype "bidirectional"))
      (node (ref "R6") (pin "2") (pinfunction "2_2") (pintype "bidirectional"))
      (node (ref "R8") (pin "1") (pinfunction "1_1") (pintype "bidirectional"))
      (node (ref "SJ1") (pin "1") (pinfunction "1_1") (pintype "passive"))
      (node (ref "SW1") (pin "1") (pinfunction "1_1") (pintype "passive"))
      (node (ref "SW2") (pin "1") (pinfunction "1_1") (pintype "passive"))
      (node (ref "SW3") (pin "1") (pinfunction "1_1") (pintype "passive"))
      (node (ref "TP_BAT_GND") (pin "TP") (pinfunction "TP_TP") (pintype "input"))
      (node (ref "TP_GND") (pin "TP") (pinfunction "TP_TP") (pintype "input"))
      (node (ref "U$38") (pin "2") (pinfunction "2_2") (pintype "passive"))
      (node (ref "U$39") (pin "2") (pinfunction "2_2") (pintype "passive"))
      (node (ref "U$40") (pin "1") (pinfunction "1_1") (pintype "passive"))
      (node (ref "U$41") (pin "1") (pinfunction "1_1") (pintype "passive"))
      (node (ref "U$42") (pin "1") (pinfunction "1_1") (pintype "passive"))
      (node (ref "U$43") (pin "1") (pinfunction "1_1") (pintype "passive"))
      (node (ref "U$44") (pin "1") (pinfunction "1_1") (pintype "passive"))
      (node (ref "U$45") (pin "1") (pinfunction "1_1") (pintype "passive"))
      (node (ref "U$46") (pin "1") (pinfunction "1_1") (pintype "passive"))
      (node (ref "U$47") (pin "1") (pinfunction "1_1") (pintype "passive"))
      (node (ref "U$48") (pin "1") (pinfunction "1_1") (pintype "passive"))
      (node (ref "U$49") (pin "1") (pinfunction "1_1") (pintype "passive"))
      (node (ref "U1") (pin "1") (pinfunction "CTG_1") (pintype "power_in"))
      (node (ref "U1") (pin "4") (pinfunction "GND_4") (pintype "power_in"))
      (node (ref "U1") (pin "6") (pinfunction "QSTRT_6") (pintype "input"))
      (node (ref "U1") (pin "9") (pinfunction "EP_9") (pintype "power_in"))
      (node (ref "U2") (pin "P$74") (pinfunction "VSS_PAD_P$74") (pintype "bidirectional"))
      (node (ref "U2") (pin "P$75") (pinfunction "VSS_PAD_P$75") (pintype "bidirectional"))
      (node (ref "U2") (pin "P$76") (pinfunction "VSS_PAD_P$76") (pintype "bidirectional"))
      (node (ref "U2") (pin "P$77") (pinfunction "VSS_PAD_P$77") (pintype "bidirectional"))
      (node (ref "U2") (pin "P$78") (pinfunction "VSS_PAD_P$78") (pintype "bidirectional"))
      (node (ref "U2") (pin "P$79") (pinfunction "VSS_PAD_P$79") (pintype "bidirectional"))
      (node (ref "U2") (pin "P$80") (pinfunction "VSS_PAD_P$80") (pintype "bidirectional"))
      (node (ref "U2") (pin "P$81") (pinfunction "VSS_PAD_P$81") (pintype "bidirectional"))
      (node (ref "U2") (pin "P$82") (pinfunction "VSS_PAD_P$82") (pintype "bidirectional"))
      (node (ref "U2") (pin "P$83") (pinfunction "VSS_PAD_P$83") (pintype "bidirectional"))
      (node (ref "U2") (pin "P$84") (pinfunction "VSS_PAD_P$84") (pintype "bidirectional"))
      (node (ref "U2") (pin "P$85") (pinfunction "VSS_PAD_P$85") (pintype "bidirectional"))
      (node (ref "U2") (pin "P$86") (pinfunction "VSS_PAD_P$86") (pintype "bidirectional"))
      (node (ref "U2") (pin "P$87") (pinfunction "VSS_PAD_P$87") (pintype "bidirectional"))
      (node (ref "U2") (pin "P$88") (pinfunction "VSS_PAD_P$88") (pintype "bidirectional"))
      (node (ref "U2") (pin "P$89") (pinfunction "VSS_PAD_P$89") (pintype "bidirectional"))
      (node (ref "U2") (pin "P$90") (pinfunction "VSS_PAD_P$90") (pintype "bidirectional"))
      (node (ref "U2") (pin "P$B7") (pinfunction "VSS_P$B7") (pintype "power_in"))
      (node (ref "U2") (pin "P$F23") (pinfunction "VSS_PA_P$F23") (pintype "bidirectional"))
      (node (ref "X1") (pin "2") (pinfunction "2_2") (pintype "passive"))
      (node (ref "X1") (pin "4") (pinfunction "4_4") (pintype "passive"))
    )
    (net (code "15") (name "HAPTIC_EN") (class "Default")
      (node (ref "IC4") (pin "A1") (pinfunction "EN_A1") (pintype "bidirectional"))
      (node (ref "U2") (pin "P$U1") (pinfunction "P0.12_P$U1") (pintype "bidirectional"))
    )
    (net (code "16") (name "IMU_INT1") (class "Default")
      (node (ref "IC3") (pin "5") (pinfunction "INT1_5") (pintype "bidirectional"))
      (node (ref "U2") (pin "P$N1") (pinfunction "P0.08_P$N1") (pintype "bidirectional"))
    )
    (net (code "17") (name "IMU_INT2") (class "Default")
      (node (ref "IC3") (pin "6") (pinfunction "INT2_6") (pintype "bidirectional"))
      (node (ref "U2") (pin "P$P2") (pinfunction "P1.08_P$P2") (pintype "bidirectional"))
    )
    (net (code "18") (name "LX1") (class "Default")
      (node (ref "IC2") (pin "B2") (pinfunction "SW1_1_B2") (pintype "bidirectional"))
      (node (ref "IC2") (pin "B3") (pinfunction "SW1_2_B3") (pintype "bidirectional"))
      (node (ref "L1") (pin "1") (pinfunction "1_1") (pintype "bidirectional"))
    )
    (net (code "19") (name "LX2") (class "Default")
      (node (ref "IC2") (pin "D2") (pinfunction "SW2_1_D2") (pintype "bidirectional"))
      (node (ref "IC2") (pin "D3") (pinfunction "SW2_2_D3") (pintype "bidirectional"))
      (node (ref "L1") (pin "2") (pinfunction "2_2") (pintype "bidirectional"))
    )
    (net (code "20") (name "MOSI") (class "Default")
      (node (ref "J2") (pin "14") (pinfunction "14_14") (pintype "bidirectional"))
      (node (ref "U2") (pin "P$B13") (pinfunction "P0.03/AIN1_P$B13") (pintype "bidirectional"))
    )
    (net (code "21") (name "Net-(ANT1-FEED)") (class "Default")
      (node (ref "ANT1") (pin "1") (pinfunction "FEED_1") (pintype "input"))
      (node (ref "C22") (pin "1") (pinfunction "1_1") (pintype "passive"))
      (node (ref "C23") (pin "1") (pinfunction "1_1") (pintype "passive"))
      (node (ref "L4") (pin "2") (pinfunction "2_2") (pintype "passive"))
    )
    (net (code "22") (name "Net-(D2-A)") (class "Default")
      (node (ref "C31") (pin "1") (pinfunction "1_1") (pintype "passive"))
      (node (ref "D2") (pin "2") (pinfunction "A_2") (pintype "bidirectional"))
      (node (ref "D3") (pin "1") (pinfunction "K_1") (pintype "bidirectional"))
    )
    (net (code "23") (name "Net-(D4-A)") (class "Default")
      (node (ref "C31") (pin "2") (pinfunction "2_2") (pintype "passive"))
      (node (ref "D4") (pin "2") (pinfunction "A_2") (pintype "bidirectional"))
      (node (ref "Q2") (pin "3") (pinfunction "D_3") (pintype "bidirectional"))
      (node (ref "U$30") (pin "2") (pinfunction "2_2") (pintype "passive"))
    )
    (net (code "24") (name "Net-(IC1-TS{slash}MR)") (class "Default")
      (node (ref "IC1") (pin "D1") (pinfunction "TS/MR_D1") (pintype "bidirectional"))
      (node (ref "R1") (pin "2") (pinfunction "2_2") (pintype "bidirectional"))
    )
    (net (code "25") (name "Net-(IC2-SCL)") (class "Default")
      (node (ref "IC2") (pin "D1") (pinfunction "SCL_D1") (pintype "bidirectional"))
      (node (ref "R4") (pin "1") (pinfunction "1_1") (pintype "bidirectional"))
    )
    (net (code "26") (name "Net-(IC2-SDA)") (class "Default")
      (node (ref "IC2") (pin "E1") (pinfunction "SDA_E1") (pintype "bidirectional"))
      (node (ref "R5") (pin "1") (pinfunction "1_1") (pintype "bidirectional"))
    )
    (net (code "27") (name "Net-(IC3-SDO)") (class "Default")
      (node (ref "IC3") (pin "1") (pinfunction "SDO_1") (pintype "bidirectional"))
      (node (ref "R6") (pin "1") (pinfunction "1_1") (pintype "bidirectional"))
    )
    (net (code "28") (name "Net-(IC4-REG)") (class "Default")
      (node (ref "C32") (pin "1") (pinfunction "1_1") (pintype "passive"))
      (node (ref "IC4") (pin "A2") (pinfunction "REG_A2") (pintype "bidirectional"))
    )
    (net (code "29") (name "Net-(J2-Pad4)") (class "Default")
      (node (ref "J2") (pin "4") (pinfunction "4_4") (pintype "bidirectional"))
      (node (ref "U$40") (pin "2") (pinfunction "2_2") (pintype "passive"))
    )
    (net (code "30") (name "Net-(J2-Pad5)") (class "Default")
      (node (ref "J2") (pin "5") (pinfunction "5_5") (pintype "bidirectional"))
      (node (ref "U$41") (pin "2") (pinfunction "2_2") (pintype "passive"))
    )
    (net (code "31") (name "Net-(J2-Pad18)") (class "Default")
      (node (ref "J2") (pin "18") (pinfunction "18_18") (pintype "bidirectional"))
      (node (ref "U$43") (pin "2") (pinfunction "2_2") (pintype "passive"))
    )
    (net (code "32") (name "Net-(J2-Pad19)") (class "Default")
      (node (ref "J2") (pin "19") (pinfunction "19_19") (pintype "bidirectional"))
      (node (ref "U$44") (pin "2") (pinfunction "2_2") (pintype "passive"))
    )
    (net (code "33") (name "Net-(J2-Pad20)") (class "Default")
      (node (ref "J2") (pin "20") (pinfunction "20_20") (pintype "bidirectional"))
      (node (ref "U$45") (pin "2") (pinfunction "2_2") (pintype "passive"))
    )
    (net (code "34") (name "Net-(J2-Pad22)") (class "Default")
      (node (ref "J2") (pin "22") (pinfunction "22_22") (pintype "bidirectional"))
      (node (ref "U$47") (pin "2") (pinfunction "2_2") (pintype "passive"))
    )
    (net (code "35") (name "Net-(J2-Pad24)") (class "Default")
      (node (ref "J2") (pin "24") (pinfunction "24_24") (pintype "bidirectional"))
      (node (ref "U$49") (pin "2") (pinfunction "2_2") (pintype "passive"))
    )
    (net (code "36") (name "Net-(J3-CC1)") (class "Default")
      (node (ref "J3") (pin "A5") (pinfunction "CC1_A5") (pintype "bidirectional"))
      (node (ref "R15") (pin "2") (pinfunction "2_2") (pintype "bidirectional"))
    )
    (net (code "37") (name "Net-(J3-CC2)") (class "Default")
      (node (ref "J3") (pin "B5") (pinfunction "CC2_B5") (pintype "bidirectional"))
      (node (ref "R14") (pin "1") (pinfunction "1_1") (pintype "bidirectional"))
    )
    (net (code "38") (name "Net-(L2-Pad2)") (class "Default")
      (node (ref "L2") (pin "2") (pinfunction "2_2") (pintype "passive"))
      (node (ref "L3") (pin "1") (pinfunction "1_1") (pintype "passive"))
    )
    (net (code "39") (name "Net-(R10-Pad2)") (class "Default")
      (node (ref "R10") (pin "2") (pinfunction "2_2") (pintype "bidirectional"))
      (node (ref "R9") (pin "1") (pinfunction "1_1") (pintype "bidirectional"))
      (node (ref "SJ1") (pin "2") (pinfunction "2_2") (pintype "passive"))
    )
    (net (code "40") (name "Net-(U2-ANT)") (class "Default")
      (node (ref "C24") (pin "1") (pinfunction "1_1") (pintype "passive"))
      (node (ref "L4") (pin "1") (pinfunction "1_1") (pintype "passive"))
      (node (ref "U2") (pin "P$H23") (pinfunction "ANT_P$H23") (pintype "bidirectional"))
    )
    (net (code "41") (name "Net-(U2-DCC)") (class "Default")
      (node (ref "L2") (pin "1") (pinfunction "1_1") (pintype "passive"))
      (node (ref "U2") (pin "P$B3") (pinfunction "DCC_P$B3") (pintype "output"))
    )
    (net (code "42") (name "Net-(U2-DEC1)") (class "Default")
      (node (ref "C12") (pin "1") (pinfunction "1_1") (pintype "passive"))
      (node (ref "U2") (pin "P$C1") (pinfunction "DEC1_P$C1") (pintype "power_in"))
    )
    (net (code "43") (name "Net-(U2-DEC2)") (class "Default")
      (node (ref "C16") (pin "1") (pinfunction "1_1") (pintype "passive"))
      (node (ref "U2") (pin "P$A18") (pinfunction "DEC2_P$A18") (pintype "bidirectional"))
    )
    (net (code "44") (name "Net-(U2-DEC3)") (class "Default")
      (node (ref "C18") (pin "1") (pinfunction "1_1") (pintype "passive"))
      (node (ref "U2") (pin "P$D23") (pinfunction "DEC3_P$D23") (pintype "bidirectional"))
    )
    (net (code "45") (name "Net-(U2-DEC3V3)") (class "Default")
      (node (ref "C27") (pin "1") (pinfunction "1_1") (pintype "passive"))
      (node (ref "U2") (pin "P$AC5") (pinfunction "DEC3V3_P$AC5") (pintype "bidirectional"))
    )
    (net (code "46") (name "Net-(U2-DEC4)") (class "Default")
      (node (ref "C14") (pin "1") (pinfunction "1_1") (pintype "passive"))
      (node (ref "C15") (pin "1") (pinfunction "1_1") (pintype "passive"))
      (node (ref "C19") (pin "1") (pinfunction "1_1") (pintype "passive"))
      (node (ref "L3") (pin "2") (pinfunction "2_2") (pintype "passive"))
      (node (ref "U2") (pin "P$B5") (pinfunction "DEC4_P$B5") (pintype "power_in"))
      (node (ref "U2") (pin "P$E24") (pinfunction "DEC6_P$E24") (pintype "bidirectional"))
    )
    (net (code "47") (name "Net-(U2-DEC5)") (class "Default")
      (node (ref "C25") (pin "1") (pinfunction "1_1") (pintype "passive"))
      (node (ref "U2") (pin "P$N24") (pinfunction "DEC5_P$N24") (pintype "bidirectional"))
    )
    (net (code "48") (name "Net-(U2-P0.00{slash}XL1)") (class "Default")
      (node (ref "C10") (pin "2") (pinfunction "2_2") (pintype "passive"))
      (node (ref "U2") (pin "P$D2") (pinfunction "P0.00/XL1_P$D2") (pintype "bidirectional"))
      (node (ref "X2") (pin "1") (pinfunction "1_1") (pintype "passive"))
    )
    (net (code "49") (name "Net-(U2-P0.01{slash}XL2)") (class "Default")
      (node (ref "C11") (pin "2") (pinfunction "2_2") (pintype "passive"))
      (node (ref "U2") (pin "P$F2") (pinfunction "P0.01/XL2_P$F2") (pintype "bidirectional"))
      (node (ref "X2") (pin "2") (pinfunction "2_2") (pintype "passive"))
    )
    (net (code "50") (name "Net-(U2-XC1)") (class "Default")
      (node (ref "C21") (pin "1") (pinfunction "1_1") (pintype "passive"))
      (node (ref "U2") (pin "P$B24") (pinfunction "XC1_P$B24") (pintype "input"))
      (node (ref "X1") (pin "1") (pinfunction "1_1") (pintype "passive"))
    )
    (net (code "51") (name "Net-(U2-XC2)") (class "Default")
      (node (ref "C20") (pin "1") (pinfunction "1_1") (pintype "passive"))
      (node (ref "U2") (pin "P$A23") (pinfunction "XC2_P$A23") (pintype "output"))
      (node (ref "X1") (pin "3") (pinfunction "3_3") (pintype "passive"))
    )
    (net (code "52") (name "OUT+") (class "Default")
      (node (ref "IC4") (pin "A3") (pinfunction "OUT+_A3") (pintype "bidirectional"))
      (node (ref "TP_OP") (pin "TP") (pinfunction "TP_TP") (pintype "input"))
    )
    (net (code "53") (name "OUT-") (class "Default")
      (node (ref "IC4") (pin "C3") (pinfunction "OUT-_C3") (pintype "bidirectional"))
      (node (ref "TP_ON") (pin "TP") (pinfunction "TP_TP") (pintype "input"))
    )
    (net (code "54") (name "P0.04") (class "Default")
      (node (ref "U2") (pin "P$J1") (pinfunction "P0.04/AIN2_P$J1") (pintype "bidirectional"))
    )
    (net (code "55") (name "P0.09") (class "Default")
      (node (ref "U2") (pin "P$L24") (pinfunction "P0.09/NFC1_P$L24") (pintype "bidirectional"))
    )
    (net (code "56") (name "P0.13") (class "Default")
      (node (ref "C36") (pin "1") (pinfunction "1_1") (pintype "passive"))
      (node (ref "R11") (pin "1") (pinfunction "1_1") (pintype "bidirectional"))
      (node (ref "SW1") (pin "2") (pinfunction "2_2") (pintype "passive"))
      (node (ref "U2") (pin "P$AD8") (pinfunction "P0.13_P$AD8") (pintype "bidirectional"))
    )
    (net (code "57") (name "P0.14") (class "Default")
      (node (ref "U2") (pin "P$AC9") (pinfunction "P0.14_P$AC9") (pintype "bidirectional"))
    )
    (net (code "58") (name "P0.19") (class "Default")
      (node (ref "U2") (pin "P$AC15") (pinfunction "P0.19_P$AC15") (pintype "bidirectional"))
    )
    (net (code "59") (name "P0.20") (class "Default")
      (node (ref "U2") (pin "P$AD16") (pinfunction "P0.20_P$AD16") (pintype "bidirectional"))
    )
    (net (code "60") (name "P0.21") (class "Default")
      (node (ref "U2") (pin "P$AC17") (pinfunction "P0.21_P$AC17") (pintype "bidirectional"))
    )
    (net (code "61") (name "P0.22") (class "Default")
      (node (ref "U2") (pin "P$AD18") (pinfunction "P0.22_P$AD18") (pintype "bidirectional"))
    )
    (net (code "62") (name "P0.23") (class "Default")
      (node (ref "U2") (pin "P$AC19") (pinfunction "P0.23_P$AC19") (pintype "bidirectional"))
    )
    (net (code "63") (name "P0.24") (class "Default")
      (node (ref "U2") (pin "P$AD20") (pinfunction "P0.24_P$AD20") (pintype "bidirectional"))
    )
    (net (code "64") (name "P0.25") (class "Default")
      (node (ref "U2") (pin "P$AC21") (pinfunction "P0.25_P$AC21") (pintype "bidirectional"))
    )
    (net (code "65") (name "P0.26") (class "Default")
      (node (ref "U2") (pin "P$G1") (pinfunction "P0.26_P$G1") (pintype "bidirectional"))
    )
    (net (code "66") (name "P0.27") (class "Default")
      (node (ref "U2") (pin "P$H2") (pinfunction "P0.27_P$H2") (pintype "bidirectional"))
    )
    (net (code "67") (name "P0.28") (class "Default")
      (node (ref "U2") (pin "P$B11") (pinfunction "P0.28/AIN4_P$B11") (pintype "bidirectional"))
    )
    (net (code "68") (name "P0.29") (class "Default")
      (node (ref "U2") (pin "P$A10") (pinfunction "P0.29/AIN5_P$A10") (pintype "bidirectional"))
    )
    (net (code "69") (name "P0.30") (class "Default")
      (node (ref "U2") (pin "P$B9") (pinfunction "P0.30/AIN6_P$B9") (pintype "bidirectional"))
    )
    (net (code "70") (name "P0.31") (class "Default")
      (node (ref "U2") (pin "P$A8") (pinfunction "P0.31/AIN7_P$A8") (pintype "bidirectional"))
    )
    (net (code "71") (name "P1.01") (class "Default")
      (node (ref "Q1") (pin "1") (pinfunction "G_1") (pintype "bidirectional"))
      (node (ref "R7") (pin "1") (pinfunction "1_1") (pintype "bidirectional"))
      (node (ref "U2") (pin "P$Y23") (pinfunction "P1.01_P$Y23") (pintype "bidirectional"))
    )
    (net (code "72") (name "P1.02") (class "Default")
      (node (ref "C34") (pin "1") (pinfunction "1_1") (pintype "passive"))
      (node (ref "R13") (pin "1") (pinfunction "1_1") (pintype "bidirectional"))
      (node (ref "SW3") (pin "2") (pinfunction "2_2") (pintype "passive"))
      (node (ref "U2") (pin "P$W24") (pinfunction "P1.02_P$W24") (pintype "bidirectional"))
    )
    (net (code "73") (name "P1.03") (class "Default")
      (node (ref "U2") (pin "P$V23") (pinfunction "P1.03_P$V23") (pintype "bidirectional"))
    )
    (net (code "74") (name "P1.04") (class "Default")
      (node (ref "U2") (pin "P$U24") (pinfunction "P1.04_P$U24") (pintype "bidirectional"))
    )
    (net (code "75") (name "P1.05") (class "Default")
      (node (ref "U2") (pin "P$T23") (pinfunction "P1.05_P$T23") (pintype "bidirectional"))
    )
    (net (code "76") (name "P1.06") (class "Default")
      (node (ref "U2") (pin "P$R24") (pinfunction "P1.06_P$R24") (pintype "bidirectional"))
    )
    (net (code "77") (name "P1.07") (class "Default")
      (node (ref "U2") (pin "P$P23") (pinfunction "P1.07_P$P23") (pintype "bidirectional"))
    )
    (net (code "78") (name "P1.09") (class "Default")
      (node (ref "U2") (pin "P$R1") (pinfunction "P1.09_P$R1") (pintype "bidirectional"))
    )
    (net (code "79") (name "P1.10") (class "Default")
      (node (ref "U2") (pin "P$A20") (pinfunction "P1.10_P$A20") (pintype "bidirectional"))
    )
    (net (code "80") (name "P1.11") (class "Default")
      (node (ref "U2") (pin "P$B19") (pinfunction "P1.11_P$B19") (pintype "bidirectional"))
    )
    (net (code "81") (name "P1.12") (class "Default")
      (node (ref "U2") (pin "P$B17") (pinfunction "P1.12_P$B17") (pintype "bidirectional"))
    )
    (net (code "82") (name "P1.13") (class "Default")
      (node (ref "U2") (pin "P$A16") (pinfunction "P1.13_P$A16") (pintype "bidirectional"))
    )
    (net (code "83") (name "P1.14") (class "Default")
      (node (ref "C35") (pin "1") (pinfunction "1_1") (pintype "passive"))
      (node (ref "R12") (pin "1") (pinfunction "1_1") (pintype "bidirectional"))
      (node (ref "SW2") (pin "2") (pinfunction "2_2") (pintype "passive"))
      (node (ref "U2") (pin "P$B15") (pinfunction "P1.14_P$B15") (pintype "bidirectional"))
    )
    (net (code "84") (name "P1.15") (class "Default")
      (node (ref "U2") (pin "P$A14") (pinfunction "P1.15_P$A14") (pintype "bidirectional"))
    )
    (net (code "85") (name "PMIC_INT") (class "Default")
      (node (ref "IC1") (pin "A1") (pinfunction "~{INT}_A1") (pintype "bidirectional"))
      (node (ref "U2") (pin "P$T2") (pinfunction "P0.11_P$T2") (pintype "bidirectional"))
    )
    (net (code "86") (name "PREVGH") (class "Default")
      (node (ref "D4") (pin "1") (pinfunction "K_1") (pintype "bidirectional"))
      (node (ref "J2") (pin "21") (pinfunction "21_21") (pintype "bidirectional"))
      (node (ref "U$46") (pin "2") (pinfunction "2_2") (pintype "passive"))
    )
    (net (code "87") (name "PREVGL") (class "Default")
      (node (ref "D3") (pin "2") (pinfunction "A_2") (pintype "bidirectional"))
      (node (ref "J2") (pin "23") (pinfunction "23_23") (pintype "bidirectional"))
      (node (ref "U$48") (pin "2") (pinfunction "2_2") (pintype "passive"))
    )
    (net (code "88") (name "RESE") (class "Default")
      (node (ref "J2") (pin "3") (pinfunction "3_3") (pintype "bidirectional"))
      (node (ref "Q2") (pin "2") (pinfunction "S_2") (pintype "bidirectional"))
      (node (ref "R9") (pin "2") (pinfunction "2_2") (pintype "bidirectional"))
    )
    (net (code "89") (name "RESET") (class "Default")
      (node (ref "J1") (pin "6") (pinfunction "6_6") (pintype "bidirectional"))
      (node (ref "TP_RESET") (pin "TP") (pinfunction "TP_TP") (pintype "input"))
      (node (ref "U2") (pin "P$AC13") (pinfunction "P0.18/RESET_P$AC13") (pintype "bidirectional"))
    )
    (net (code "90") (name "SCK") (class "Default")
      (node (ref "J2") (pin "13") (pinfunction "13_13") (pintype "bidirectional"))
      (node (ref "U2") (pin "P$A12") (pinfunction "P0.02/AIN0_P$A12") (pintype "bidirectional"))
    )
    (net (code "91") (name "SCL") (class "Default")
      (node (ref "IC1") (pin "B1") (pinfunction "SCL_B1") (pintype "bidirectional"))
      (node (ref "IC3") (pin "12") (pinfunction "SCX_12") (pintype "bidirectional"))
      (node (ref "IC4") (pin "C1") (pinfunction "SCL_C1") (pintype "bidirectional"))
      (node (ref "R2") (pin "2") (pinfunction "2_2") (pintype "bidirectional"))
      (node (ref "R4") (pin "2") (pinfunction "2_2") (pintype "bidirectional"))
      (node (ref "TP_SCL") (pin "TP") (pinfunction "TP_TP") (pintype "input"))
      (node (ref "U1") (pin "7") (pinfunction "SCL_7") (pintype "input"))
      (node (ref "U2") (pin "P$M2") (pinfunction "P0.07_P$M2") (pintype "bidirectional"))
    )
    (net (code "92") (name "SDA") (class "Default")
      (node (ref "IC1") (pin "C1") (pinfunction "SDA_C1") (pintype "bidirectional"))
      (node (ref "IC3") (pin "2") (pinfunction "SDX_2") (pintype "bidirectional"))
      (node (ref "IC4") (pin "B2") (pinfunction "SDA_B2") (pintype "bidirectional"))
      (node (ref "R3") (pin "2") (pinfunction "2_2") (pintype "bidirectional"))
      (node (ref "R5") (pin "2") (pinfunction "2_2") (pintype "bidirectional"))
      (node (ref "TP_SDA") (pin "TP") (pinfunction "TP_TP") (pintype "input"))
      (node (ref "U1") (pin "8") (pinfunction "SDA_8") (pintype "bidirectional"))
      (node (ref "U2") (pin "P$L1") (pinfunction "P0.06_P$L1") (pintype "bidirectional"))
    )
    (net (code "93") (name "SWDCLK") (class "Default")
      (node (ref "J1") (pin "4") (pinfunction "4_4") (pintype "bidirectional"))
      (node (ref "TP_SWDCLK") (pin "TP") (pinfunction "TP_TP") (pintype "input"))
      (node (ref "U2") (pin "P$AA24") (pinfunction "SWDCLK_P$AA24") (pintype "input"))
    )
    (net (code "94") (name "SWDIO") (class "Default")
      (node (ref "J1") (pin "2") (pinfunction "2_2") (pintype "bidirectional"))
      (node (ref "TP_SWDIO") (pin "TP") (pinfunction "TP_TP") (pintype "input"))
      (node (ref "U2") (pin "P$AC24") (pinfunction "SWDIO_P$AC24") (pintype "bidirectional"))
    )
    (net (code "95") (name "SWO") (class "Default")
      (node (ref "TP_SWO") (pin "TP") (pinfunction "TP_TP") (pintype "input"))
      (node (ref "U2") (pin "P$AD22") (pinfunction "P1.00_P$AD22") (pintype "bidirectional"))
    )
    (net (code "96") (name "VBAT") (class "Default")
      (node (ref "C3") (pin "1") (pinfunction "1_1") (pintype "passive"))
      (node (ref "C37") (pin "1") (pinfunction "1_1") (pintype "passive"))
      (node (ref "IC1") (pin "C2") (pinfunction "BAT_C2") (pintype "bidirectional"))
      (node (ref "TP_VBAT") (pin "TP") (pinfunction "TP_TP") (pintype "input"))
      (node (ref "U1") (pin "2") (pinfunction "CELL_2") (pintype "power_in"))
      (node (ref "U1") (pin "3") (pinfunction "VDD_3") (pintype "power_in"))
    )
    (net (code "97") (name "VBUS") (class "Default")
      (node (ref "C1") (pin "1") (pinfunction "1_1") (pintype "passive"))
      (node (ref "C7") (pin "1") (pinfunction "1_1") (pintype "passive"))
      (node (ref "D1") (pin "5") (pinfunction "VBUS_5") (pintype "bidirectional"))
      (node (ref "IC1") (pin "A2") (pinfunction "IN_A2") (pintype "bidirectional"))
      (node (ref "J3") (pin "A4_B9") (pinfunction "VBUS_A4_B9") (pintype "power_in"))
      (node (ref "J3") (pin "A9_B4") (pinfunction "VBUS_A9_B4") (pintype "power_in"))
      (node (ref "U$38") (pin "1") (pinfunction "1_1") (pintype "passive"))
      (node (ref "U$39") (pin "1") (pinfunction "1_1") (pintype "passive"))
      (node (ref "U2") (pin "P$AD2") (pinfunction "VBUS_P$AD2") (pintype "power_in"))
    )
    (net (code "98") (name "VREG") (class "Default")
      (node (ref "C2") (pin "1") (pinfunction "1_1") (pintype "passive"))
      (node (ref "C4") (pin "2") (pinfunction "2_2") (pintype "passive"))
      (node (ref "C8") (pin "2") (pinfunction "2_2") (pintype "passive"))
      (node (ref "IC1") (pin "B2") (pinfunction "SYS_B2") (pintype "bidirectional"))
      (node (ref "IC2") (pin "A1") (pinfunction "EN_A1") (pintype "bidirectional"))
      (node (ref "IC2") (pin "A2") (pinfunction "VIN_1_A2") (pintype "bidirectional"))
      (node (ref "IC2") (pin "A3") (pinfunction "VIN_2_A3") (pintype "bidirectional"))
      (node (ref "TP_VREG") (pin "TP") (pinfunction "TP_TP") (pintype "input"))
    )
    (net (code "99") (name "unconnected-(ANT1-NC-Pad2)") (class "Default")
      (node (ref "ANT1") (pin "2") (pinfunction "NC_2") (pintype "no_connect"))
    )
    (net (code "100") (name "unconnected-(IC3-ASCL-Pad11)") (class "Default")
      (node (ref "IC3") (pin "11") (pinfunction "ASCL_11") (pintype "bidirectional"))
    )
    (net (code "101") (name "unconnected-(IC3-ASDA-Pad4)") (class "Default")
      (node (ref "IC3") (pin "4") (pinfunction "ASDA_4") (pintype "bidirectional"))
    )
    (net (code "102") (name "unconnected-(J2-Pad1)") (class "Default")
      (node (ref "J2") (pin "1") (pinfunction "1_1") (pintype "bidirectional"))
    )
    (net (code "103") (name "unconnected-(J2-Pad6)") (class "Default")
      (node (ref "J2") (pin "6") (pinfunction "6_6") (pintype "bidirectional"))
    )
    (net (code "104") (name "unconnected-(J2-Pad7)") (class "Default")
      (node (ref "J2") (pin "7") (pinfunction "7_7") (pintype "bidirectional"))
    )
    (net (code "105") (name "unconnected-(J3-SBU1-PadA8)") (class "Default")
      (node (ref "J3") (pin "A8") (pinfunction "SBU1_A8") (pintype "bidirectional"))
    )
    (net (code "106") (name "unconnected-(J3-SBU2-PadB8)") (class "Default")
      (node (ref "J3") (pin "B8") (pinfunction "SBU2_B8") (pintype "bidirectional"))
    )
    (net (code "107") (name "unconnected-(U2-DCCH-PadP$AB2)") (class "Default")
      (node (ref "U2") (pin "P$AB2") (pinfunction "DCCH_P$AB2") (pintype "bidirectional"))
    )
  )
)
